# driver.net
KiCad netlist of a schematic drawn in Altium Designer
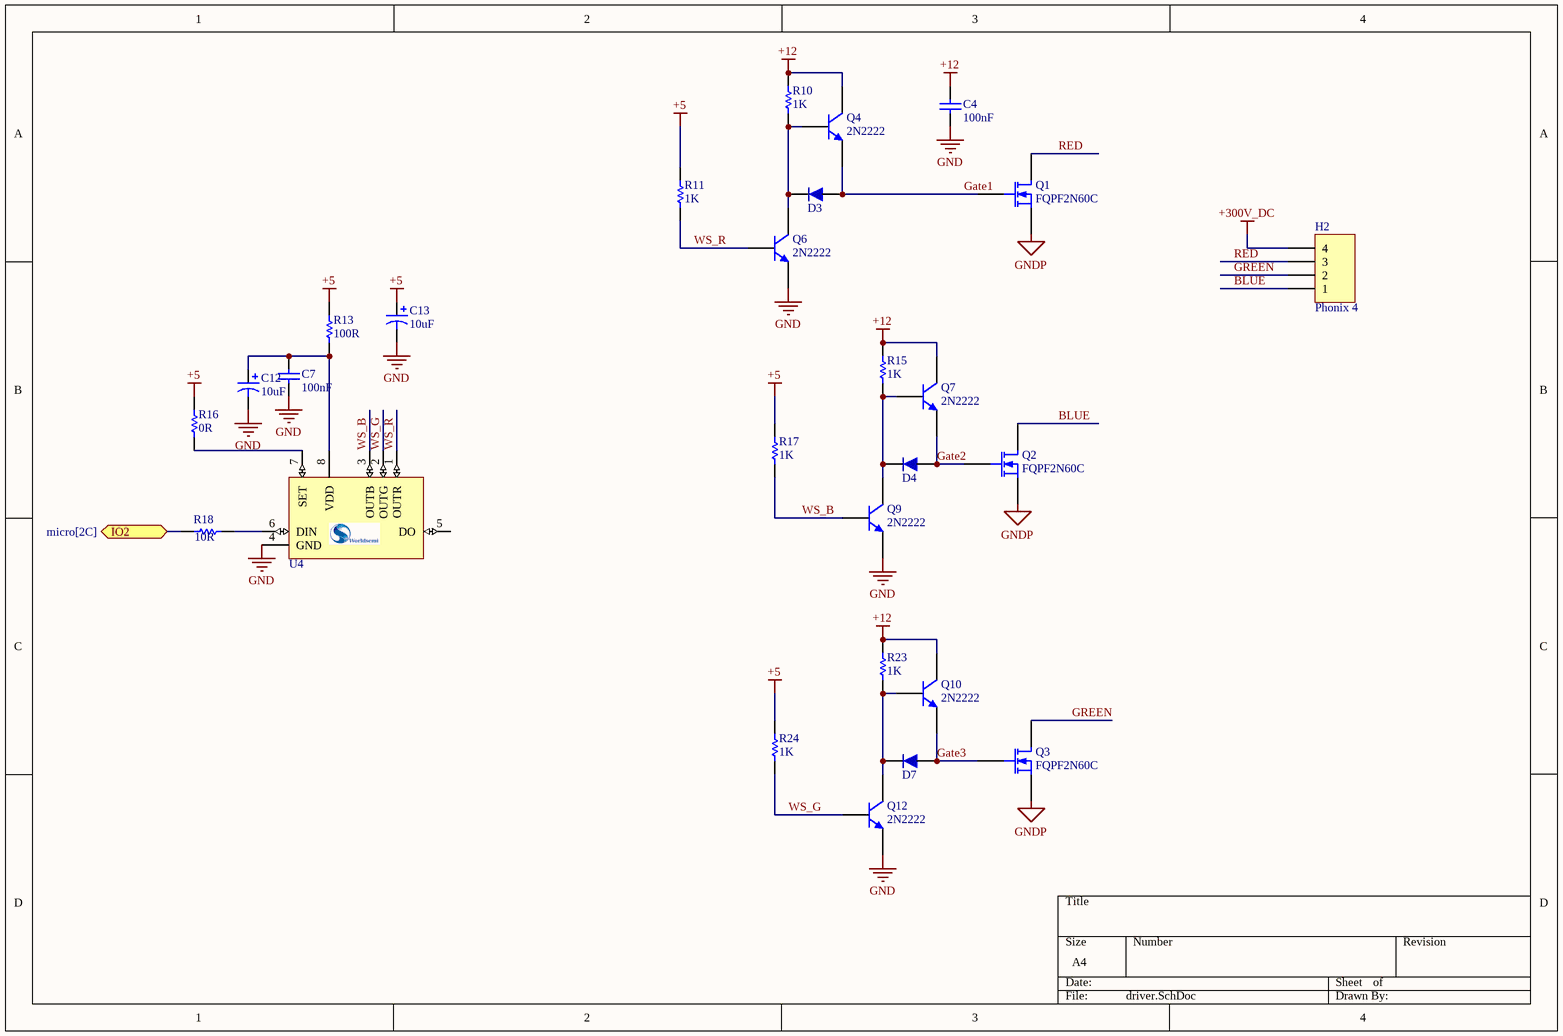
[diagram p0: driver.SchDoc]

(export (version "E")
  (design (tool "Eeschema 10.0.6"))
  (components
    (comp (ref "C4")
      (value "100nF")
      (footprint "CAP0805")
      (description "CAP seramic")
      (fields (field (name "Comment") "cap 100nF"))
      (libsource (lib "Altium library (www.AVRelec.com)") (part "Cap ceramic"))
    )
    (comp (ref "C7")
      (value "100nF")
      (footprint "CAP0805")
      (description "CAP seramic")
      (fields (field (name "Comment") "cap 100nF"))
      (libsource (lib "Altium library (www.AVRelec.com)") (part "Cap ceramic"))
    )
    (comp (ref "C12")
      (value "10uF")
      (footprint "CAP0805")
      (description "CAP seramic")
      (fields (field (name "Comment") "cap 10uF") (field (name "PUBLISHER") "Altium Limited"))
      (libsource (lib "Miscellaneous Devices") (part "Cap Pol1"))
    )
    (comp (ref "C13")
      (value "10uF")
      (footprint "CAP0805")
      (description "CAP seramic")
      (fields (field (name "Comment") "cap 10uF") (field (name "PUBLISHER") "Altium Limited"))
      (libsource (lib "Miscellaneous Devices") (part "Cap Pol1"))
    )
    (comp (ref "D3")
      (value "1n5822")
      (footprint "DIOM4629X24N")
      (description "Schotcky diode")
      (fields (field (name "MANUFACTURER") "DC COMPONENTS") (field (name "DESIGNER") "Abbas Basereh"))
      (libsource (lib "Altium (2)") (part "1n4007 SMD M7"))
    )
    (comp (ref "D4")
      (value "1n5822")
      (footprint "DIOM4629X24N")
      (description "Schotcky diode")
      (fields (field (name "MANUFACTURER") "DC COMPONENTS") (field (name "DESIGNER") "Abbas Basereh"))
      (libsource (lib "Altium (2)") (part "1n4007 SMD M7"))
    )
    (comp (ref "D7")
      (value "1n5822")
      (footprint "DIOM4629X24N")
      (description "Schotcky diode")
      (fields (field (name "MANUFACTURER") "DC COMPONENTS") (field (name "DESIGNER") "Abbas Basereh"))
      (libsource (lib "Altium (2)") (part "1n4007 SMD M7"))
    )
    (comp (ref "H2")
      (value "Phonix 4")
      (footprint "phoenix terminal R 4")
      (description "Header, 4-Pin")
      (fields (field (name "PUBLISHER") "Altium Limited"))
      (libsource (lib "Miscellaneous Connectors") (part "Header 4"))
    )
    (comp (ref "Q1")
      (value "FQPF2N60C")
      (footprint "TO-220")
      (description "N-Channel MOSFET")
      (fields (field (name "PUBLISHER") "Altium Limited"))
      (libsource (lib "Miscellaneous Devices") (part "MOSFET-N"))
    )
    (comp (ref "Q2")
      (value "FQPF2N60C")
      (footprint "TO-220")
      (description "N-Channel MOSFET")
      (fields (field (name "PUBLISHER") "Altium Limited"))
      (libsource (lib "Miscellaneous Devices") (part "MOSFET-N"))
    )
    (comp (ref "Q3")
      (value "FQPF2N60C")
      (footprint "TO-220")
      (description "N-Channel MOSFET")
      (fields (field (name "PUBLISHER") "Altium Limited"))
      (libsource (lib "Miscellaneous Devices") (part "MOSFET-N"))
    )
    (comp (ref "Q4")
      (value "2N2222")
      (footprint "SOT23_BEC_L")
      (description "NPN General Purpose Amplifier")
      (fields (field (name "PUBLISHER") "Altium Limited"))
      (libsource (lib "Miscellaneous Devices") (part "2N3904"))
    )
    (comp (ref "Q6")
      (value "2N2222")
      (footprint "SOT23_BEC_L")
      (description "NPN General Purpose Amplifier")
      (fields (field (name "PUBLISHER") "Altium Limited"))
      (libsource (lib "Miscellaneous Devices") (part "2N3904"))
    )
    (comp (ref "Q7")
      (value "2N2222")
      (footprint "SOT23_BEC_L")
      (description "NPN General Purpose Amplifier")
      (fields (field (name "PUBLISHER") "Altium Limited"))
      (libsource (lib "Miscellaneous Devices") (part "2N3904"))
    )
    (comp (ref "Q9")
      (value "2N2222")
      (footprint "SOT23_BEC_L")
      (description "NPN General Purpose Amplifier")
      (fields (field (name "PUBLISHER") "Altium Limited"))
      (libsource (lib "Miscellaneous Devices") (part "2N3904"))
    )
    (comp (ref "Q10")
      (value "2N2222")
      (footprint "SOT23_BEC_L")
      (description "NPN General Purpose Amplifier")
      (fields (field (name "PUBLISHER") "Altium Limited"))
      (libsource (lib "Miscellaneous Devices") (part "2N3904"))
    )
    (comp (ref "Q12")
      (value "2N2222")
      (footprint "SOT23_BEC_L")
      (description "NPN General Purpose Amplifier")
      (fields (field (name "PUBLISHER") "Altium Limited"))
      (libsource (lib "Miscellaneous Devices") (part "2N3904"))
    )
    (comp (ref "R10")
      (value "1K")
      (footprint "RES0805")
      (description "Resistor")
      (fields (field (name "Comment") "Res 1K") (field (name "PUBLISHER") "Altium Limited"))
      (libsource (lib "Miscellaneous Devices") (part "Res1"))
    )
    (comp (ref "R11")
      (value "1K")
      (footprint "RES0805")
      (description "Resistor")
      (fields (field (name "Comment") "Res 1K") (field (name "PUBLISHER") "Altium Limited"))
      (libsource (lib "Miscellaneous Devices") (part "Res1"))
    )
    (comp (ref "R13")
      (value "100R")
      (footprint "RES0805")
      (description "Resistor")
      (fields (field (name "Comment") "Res 100R") (field (name "PUBLISHER") "Altium Limited"))
      (libsource (lib "Miscellaneous Devices") (part "Res1"))
    )
    (comp (ref "R15")
      (value "1K")
      (footprint "RES0805")
      (description "Resistor")
      (fields (field (name "Comment") "Res 1K") (field (name "PUBLISHER") "Altium Limited"))
      (libsource (lib "Miscellaneous Devices") (part "Res1"))
    )
    (comp (ref "R16")
      (value "0R")
      (footprint "RES0805")
      (description "Resistor")
      (fields (field (name "Comment") "Res 0R") (field (name "PUBLISHER") "Altium Limited"))
      (libsource (lib "Miscellaneous Devices") (part "Res1"))
    )
    (comp (ref "R17")
      (value "1K")
      (footprint "RES0805")
      (description "Resistor")
      (fields (field (name "Comment") "Res 1K") (field (name "PUBLISHER") "Altium Limited"))
      (libsource (lib "Miscellaneous Devices") (part "Res1"))
    )
    (comp (ref "R18")
      (value "10R")
      (footprint "RES0805")
      (description "Resistor")
      (fields (field (name "Comment") "Res 10R") (field (name "PUBLISHER") "Altium Limited"))
      (libsource (lib "Miscellaneous Devices") (part "Res1"))
    )
    (comp (ref "R23")
      (value "1K")
      (footprint "RES0805")
      (description "Resistor")
      (fields (field (name "Comment") "Res 1K") (field (name "PUBLISHER") "Altium Limited"))
      (libsource (lib "Miscellaneous Devices") (part "Res1"))
    )
    (comp (ref "R24")
      (value "1K")
      (footprint "RES0805")
      (description "Resistor")
      (fields (field (name "Comment") "Res 1K") (field (name "PUBLISHER") "Altium Limited"))
      (libsource (lib "Miscellaneous Devices") (part "Res1"))
    )
    (comp (ref "U4")
      (value "WS2811 SMD")
      (footprint "8S2_N")
      (description "LED Driver IC 3 Output Linear 18.5mA Module 10PK")
      (fields (field (name "PUBLISHER") "Abbas Basereh"))
      (libsource (lib "Altium (2)") (part "WS2811 SMD"))
    )
  )
  (nets
    (net (code "1") (name "+5") (class "Default")
      (node (ref "C13") (pin "1") (pinfunction "1_1") (pintype "passive"))
      (node (ref "R11") (pin "1") (pinfunction "1_1") (pintype "passive"))
      (node (ref "R13") (pin "2") (pinfunction "2_2") (pintype "passive"))
      (node (ref "R16") (pin "2") (pinfunction "2_2") (pintype "passive"))
      (node (ref "R17") (pin "1") (pinfunction "1_1") (pintype "passive"))
      (node (ref "R24") (pin "1") (pinfunction "1_1") (pintype "passive"))
    )
    (net (code "2") (name "+12") (class "Default")
      (node (ref "C4") (pin "1") (pinfunction "1_1") (pintype "passive"))
      (node (ref "Q10") (pin "3") (pinfunction "C_3") (pintype "passive"))
      (node (ref "Q4") (pin "3") (pinfunction "C_3") (pintype "passive"))
      (node (ref "Q7") (pin "3") (pinfunction "C_3") (pintype "passive"))
      (node (ref "R10") (pin "2") (pinfunction "2_2") (pintype "passive"))
      (node (ref "R15") (pin "2") (pinfunction "2_2") (pintype "passive"))
      (node (ref "R23") (pin "2") (pinfunction "2_2") (pintype "passive"))
    )
    (net (code "3") (name "+300V_DC") (class "Default")
      (node (ref "H2") (pin "4") (pinfunction "4_4") (pintype "passive"))
    )
    (net (code "4") (name "/BLUE") (class "Default")
      (node (ref "H2") (pin "1") (pinfunction "1_1") (pintype "passive"))
      (node (ref "Q2") (pin "1") (pinfunction "D_1") (pintype "passive"))
    )
    (net (code "5") (name "/GREEN") (class "Default")
      (node (ref "H2") (pin "2") (pinfunction "2_2") (pintype "passive"))
      (node (ref "Q3") (pin "1") (pinfunction "D_1") (pintype "passive"))
    )
    (net (code "6") (name "/Gate1") (class "Default")
      (node (ref "D3") (pin "1") (pintype "passive"))
      (node (ref "Q1") (pin "2") (pinfunction "G_2") (pintype "passive"))
      (node (ref "Q4") (pin "1") (pinfunction "E_1") (pintype "passive"))
    )
    (net (code "7") (name "/Gate2") (class "Default")
      (node (ref "D4") (pin "1") (pintype "passive"))
      (node (ref "Q2") (pin "2") (pinfunction "G_2") (pintype "passive"))
      (node (ref "Q7") (pin "1") (pinfunction "E_1") (pintype "passive"))
    )
    (net (code "8") (name "/Gate3") (class "Default")
      (node (ref "D7") (pin "1") (pintype "passive"))
      (node (ref "Q10") (pin "1") (pinfunction "E_1") (pintype "passive"))
      (node (ref "Q3") (pin "2") (pinfunction "G_2") (pintype "passive"))
    )
    (net (code "9") (name "/IO2") (class "Default")
      (node (ref "R18") (pin "1") (pinfunction "1_1") (pintype "passive"))
    )
    (net (code "10") (name "/RED") (class "Default")
      (node (ref "H2") (pin "3") (pinfunction "3_3") (pintype "passive"))
      (node (ref "Q1") (pin "1") (pinfunction "D_1") (pintype "passive"))
    )
    (net (code "11") (name "/WS_B") (class "Default")
      (node (ref "Q9") (pin "2") (pinfunction "B_2") (pintype "passive"))
      (node (ref "R17") (pin "2") (pinfunction "2_2") (pintype "passive"))
      (node (ref "U4") (pin "3") (pinfunction "OUTB_3") (pintype "bidirectional"))
    )
    (net (code "12") (name "/WS_G") (class "Default")
      (node (ref "Q12") (pin "2") (pinfunction "B_2") (pintype "passive"))
      (node (ref "R24") (pin "2") (pinfunction "2_2") (pintype "passive"))
      (node (ref "U4") (pin "2") (pinfunction "OUTG_2") (pintype "bidirectional"))
    )
    (net (code "13") (name "/WS_R") (class "Default")
      (node (ref "Q6") (pin "2") (pinfunction "B_2") (pintype "passive"))
      (node (ref "R11") (pin "2") (pinfunction "2_2") (pintype "passive"))
      (node (ref "U4") (pin "1") (pinfunction "OUTR_1") (pintype "bidirectional"))
    )
    (net (code "14") (name "GND") (class "Default")
      (node (ref "C12") (pin "2") (pinfunction "2_2") (pintype "passive"))
      (node (ref "C13") (pin "2") (pinfunction "2_2") (pintype "passive"))
      (node (ref "C4") (pin "2") (pinfunction "2_2") (pintype "passive"))
      (node (ref "C7") (pin "2") (pinfunction "2_2") (pintype "passive"))
      (node (ref "Q12") (pin "1") (pinfunction "E_1") (pintype "passive"))
      (node (ref "Q6") (pin "1") (pinfunction "E_1") (pintype "passive"))
      (node (ref "Q9") (pin "1") (pinfunction "E_1") (pintype "passive"))
      (node (ref "U4") (pin "4") (pinfunction "GND_4") (pintype "power_in"))
    )
    (net (code "15") (name "GNDP") (class "Default")
      (node (ref "Q1") (pin "3") (pinfunction "S_3") (pintype "passive"))
      (node (ref "Q2") (pin "3") (pinfunction "S_3") (pintype "passive"))
      (node (ref "Q3") (pin "3") (pinfunction "S_3") (pintype "passive"))
    )
    (net (code "16") (name "Net-(Q4-B)") (class "Default")
      (node (ref "D3") (pin "2") (pintype "passive"))
      (node (ref "Q4") (pin "2") (pinfunction "B_2") (pintype "passive"))
      (node (ref "Q6") (pin "3") (pinfunction "C_3") (pintype "passive"))
      (node (ref "R10") (pin "1") (pinfunction "1_1") (pintype "passive"))
    )
    (net (code "17") (name "Net-(Q7-B)") (class "Default")
      (node (ref "D4") (pin "2") (pintype "passive"))
      (node (ref "Q7") (pin "2") (pinfunction "B_2") (pintype "passive"))
      (node (ref "Q9") (pin "3") (pinfunction "C_3") (pintype "passive"))
      (node (ref "R15") (pin "1") (pinfunction "1_1") (pintype "passive"))
    )
    (net (code "18") (name "Net-(Q10-B)") (class "Default")
      (node (ref "D7") (pin "2") (pintype "passive"))
      (node (ref "Q10") (pin "2") (pinfunction "B_2") (pintype "passive"))
      (node (ref "Q12") (pin "3") (pinfunction "C_3") (pintype "passive"))
      (node (ref "R23") (pin "1") (pinfunction "1_1") (pintype "passive"))
    )
    (net (code "19") (name "Net-(U4-DIN)") (class "Default")
      (node (ref "R18") (pin "2") (pinfunction "2_2") (pintype "passive"))
      (node (ref "U4") (pin "6") (pinfunction "DIN_6") (pintype "bidirectional"))
    )
    (net (code "20") (name "Net-(U4-SET)") (class "Default")
      (node (ref "R16") (pin "1") (pinfunction "1_1") (pintype "passive"))
      (node (ref "U4") (pin "7") (pinfunction "SET_7") (pintype "bidirectional"))
    )
    (net (code "21") (name "Net-(U4-VDD)") (class "Default")
      (node (ref "C12") (pin "1") (pinfunction "1_1") (pintype "passive"))
      (node (ref "C7") (pin "1") (pinfunction "1_1") (pintype "passive"))
      (node (ref "R13") (pin "1") (pinfunction "1_1") (pintype "passive"))
      (node (ref "U4") (pin "8") (pinfunction "VDD_8") (pintype "power_in"))
    )
    (net (code "22") (name "unconnected-(U4-DO-Pad5)") (class "Default")
      (node (ref "U4") (pin "5") (pinfunction "DO_5") (pintype "bidirectional"))
    )
  )
)
